# tps63020-buck-boost-flashlight-driver-17.net
KiCad netlist of a schematic drawn in EAGLE
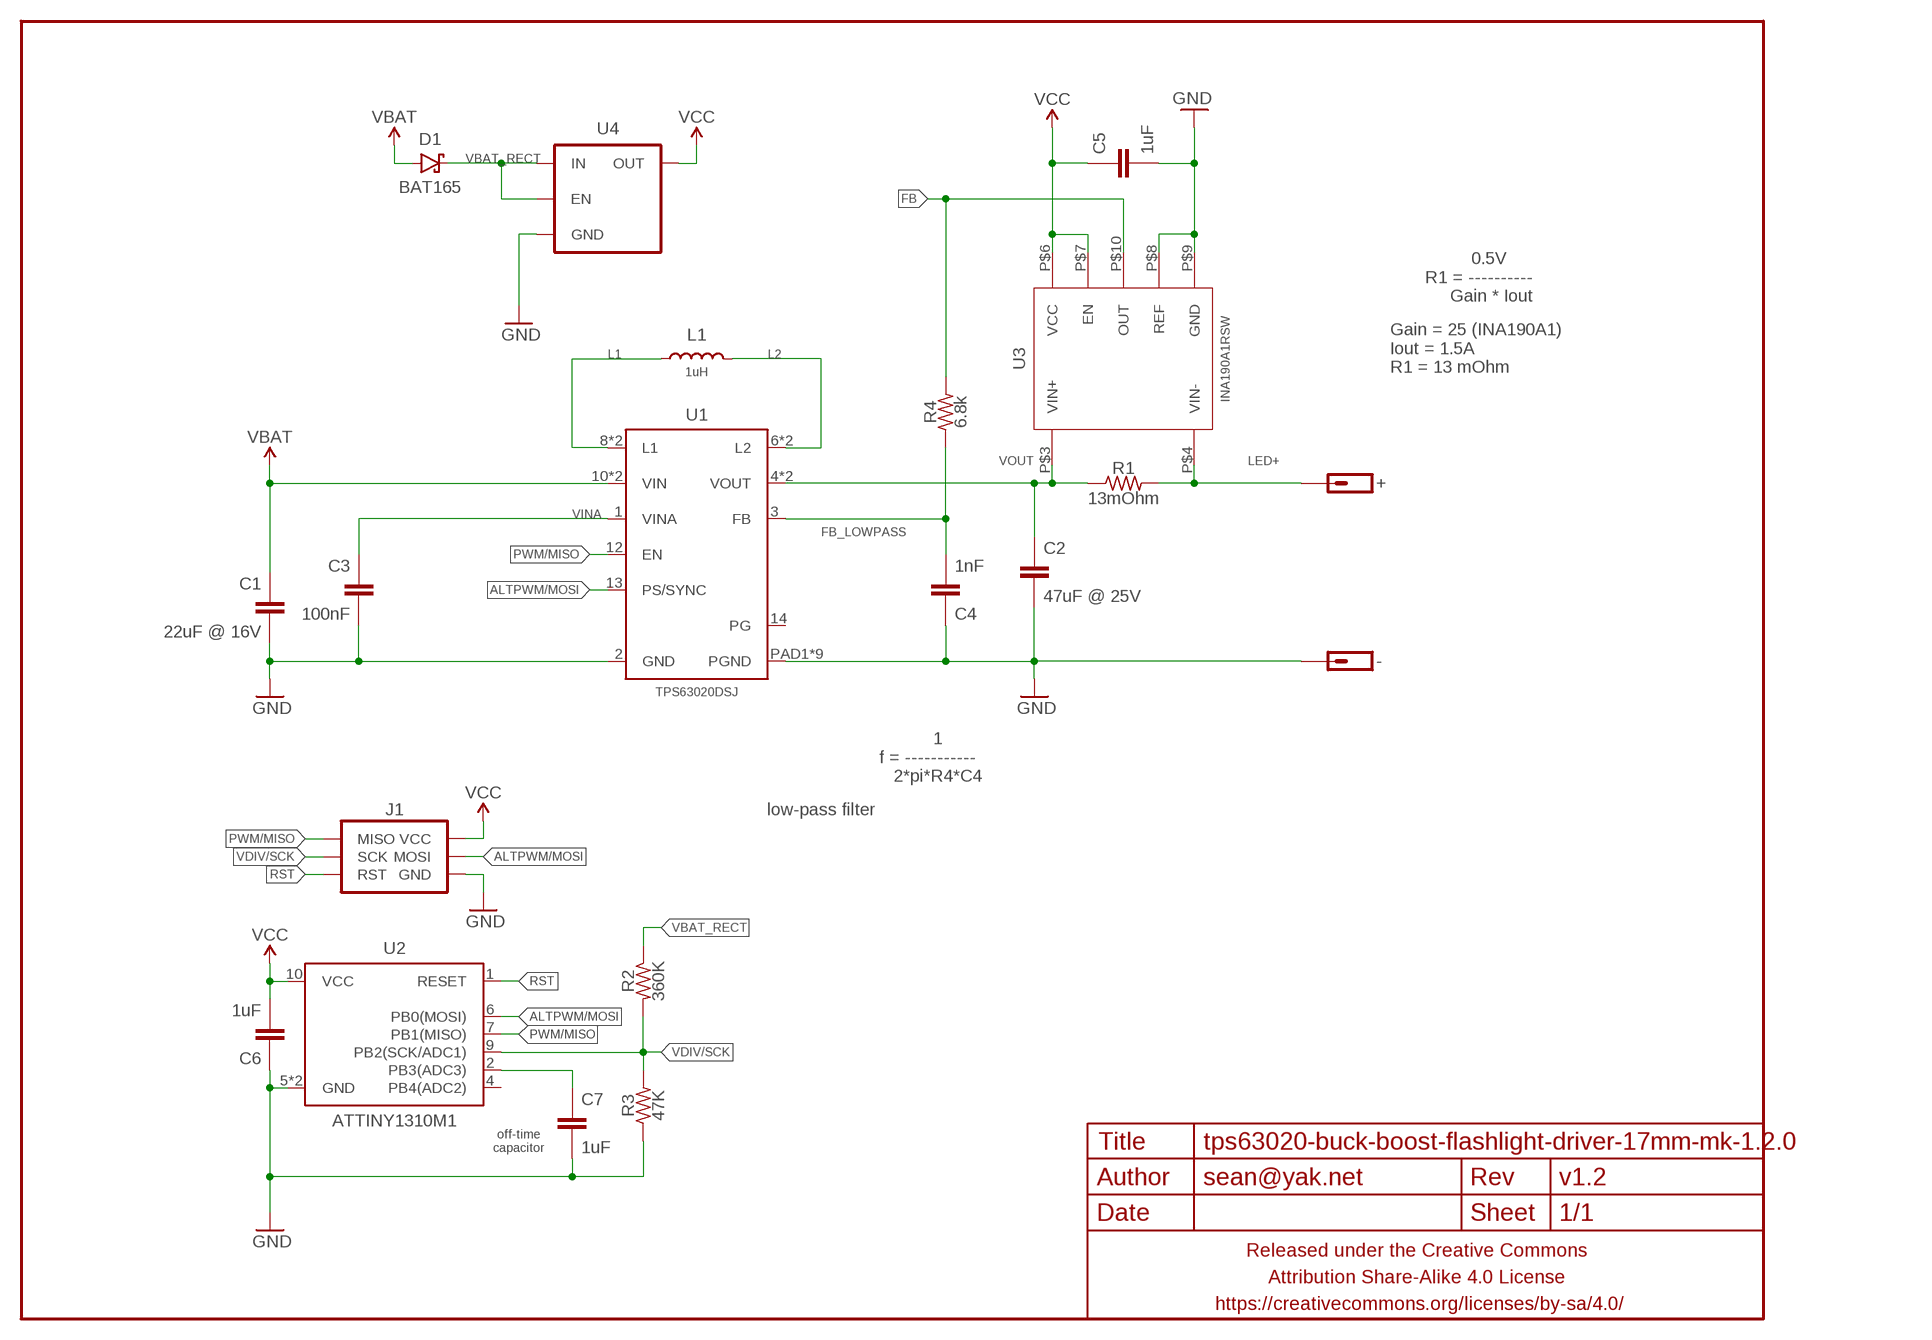
[diagram p0: schematic, sheet 1]

(export (version "E")
  (design (tool "Eeschema 10.0.6"))
  (components
    (comp (ref "+")
      (value "M01SMD-1.6MMX3.2MM")
      (footprint "eagle-import:1X01-SMD-1.6MMX3.2MM")
      (libsource (lib "eagle-import") (part "M01SMD-1.6MMX3.2MM"))
    )
    (comp (ref "-")
      (value "M01SMD-1.6MMX3.2MM")
      (footprint "eagle-import:1X01-SMD-1.6MMX3.2MM")
      (libsource (lib "eagle-import") (part "M01SMD-1.6MMX3.2MM"))
    )
    (comp (ref "C1")
      (value "22uF @ 16V")
      (footprint "eagle-import:C0805-TIGHTER")
      (libsource (lib "eagle-import") (part "CAPACITOR-CERAMICC0805-TIGHTER"))
    )
    (comp (ref "C2")
      (value "47uF @ 25V")
      (footprint "eagle-import:C1206")
      (libsource (lib "eagle-import") (part "CAPACITOR-CERAMICC1206"))
    )
    (comp (ref "C3")
      (value "100nF")
      (footprint "eagle-import:C0402")
      (libsource (lib "eagle-import") (part "CAPACITOR-CERAMICC0402"))
    )
    (comp (ref "C4")
      (value "1nF")
      (footprint "eagle-import:C0402")
      (libsource (lib "eagle-import") (part "CAPACITOR-CERAMICC0402"))
    )
    (comp (ref "C5")
      (value "1uF")
      (footprint "eagle-import:C0402")
      (libsource (lib "eagle-import") (part "CAPACITOR-CERAMICC0402"))
    )
    (comp (ref "C6")
      (value "1uF")
      (footprint "eagle-import:C0402")
      (libsource (lib "eagle-import") (part "CAPACITOR-CERAMICC0402"))
    )
    (comp (ref "C7")
      (value "1uF")
      (footprint "eagle-import:C0402")
      (libsource (lib "eagle-import") (part "CAPACITOR-CERAMICC0402"))
    )
    (comp (ref "D1")
      (value "BAT165")
      (footprint "eagle-import:SOD323-SCHOTTKY")
      (libsource (lib "eagle-import") (part "DIODE-SCHOTTKYSOD323"))
    )
    (comp (ref "FRAME1")
      (value "FRAME-LETTERNO_PACKAGE")
      (footprint "eagle-import:DUMMY")
      (fields
        (field (name "DESIGNER") "sean@yak.net")
        (field (name "VERSION") "v1.2")
        (field (name "DESIGNER_1") "sean@yak.net")
        (field (name "VERSION_1") "v1.2")
      )
      (libsource (lib "eagle-import") (part "FRAME-LETTERNO_PACKAGE"))
    )
    (comp (ref "J1")
      (value "AVR_SPI_PRG_6SMD-1.27MM")
      (footprint "eagle-import:2X3-1.27MM-SMD")
      (libsource (lib "eagle-import") (part "AVR_SPI_PRG_6SMD-1.27MM"))
    )
    (comp (ref "L1")
      (value "1uH")
      (footprint "eagle-import:XAL50X0")
      (libsource (lib "eagle-import") (part "INDUCTORXAL50X0"))
    )
    (comp (ref "R1")
      (value "13mOhm")
      (footprint "eagle-import:R1206")
      (libsource (lib "eagle-import") (part "RESISTORR1206"))
    )
    (comp (ref "R2")
      (value "360K")
      (footprint "eagle-import:R0402")
      (libsource (lib "eagle-import") (part "RESISTORR0402"))
    )
    (comp (ref "R3")
      (value "47K")
      (footprint "eagle-import:R0402")
      (libsource (lib "eagle-import") (part "RESISTORR0402"))
    )
    (comp (ref "R4")
      (value "6.8k")
      (footprint "eagle-import:R0402")
      (libsource (lib "eagle-import") (part "RESISTORR0402"))
    )
    (comp (ref "U1")
      (value "TPS63020DSJ")
      (footprint "eagle-import:VSON-14-4MMX3MM")
      (libsource (lib "eagle-import") (part "TPS63020DSJ"))
    )
    (comp (ref "U2")
      (value "ATTINY1310M1")
      (footprint "eagle-import:QFN10(2X5)")
      (libsource (lib "eagle-import") (part "ATTINY1310M1"))
    )
    (comp (ref "U3")
      (value "INA190A1RSW")
      (footprint "eagle-import:UQFN-10")
      (libsource (lib "eagle-import") (part "INA190RSW"))
    )
    (comp (ref "U4")
      (value "V_REG_ENTLV700")
      (footprint "eagle-import:SC70")
      (libsource (lib "eagle-import") (part "V_REG_ENTLV700"))
    )
  )
  (nets
    (net (code "1") (name "/FB_LOWPASS") (class "Default")
      (node (ref "C4") (pin "2") (pinfunction "2_2") (pintype "passive"))
      (node (ref "R4") (pin "1") (pinfunction "1_1") (pintype "passive"))
      (node (ref "U1") (pin "3") (pinfunction "FB_3") (pintype "bidirectional"))
    )
    (net (code "2") (name "/L1") (class "Default")
      (node (ref "L1") (pin "P$1") (pinfunction "1_P$1") (pintype "passive"))
      (node (ref "U1") (pin "8") (pinfunction "L1_8") (pintype "bidirectional"))
      (node (ref "U1") (pin "9") (pinfunction "L1_9") (pintype "bidirectional"))
    )
    (net (code "3") (name "/L2") (class "Default")
      (node (ref "L1") (pin "P$2") (pinfunction "2_P$2") (pintype "passive"))
      (node (ref "U1") (pin "6") (pinfunction "L2_6") (pintype "bidirectional"))
      (node (ref "U1") (pin "7") (pinfunction "L2_7") (pintype "bidirectional"))
    )
    (net (code "4") (name "/LED+") (class "Default")
      (node (ref "+") (pin "P$1") (pinfunction "1_P$1") (pintype "passive"))
      (node (ref "R1") (pin "2") (pinfunction "2_2") (pintype "passive"))
      (node (ref "U3") (pin "P$4") (pinfunction "VIN-_P$4") (pintype "bidirectional"))
    )
    (net (code "5") (name "/VINA") (class "Default")
      (node (ref "C3") (pin "1") (pinfunction "1_1") (pintype "passive"))
      (node (ref "U1") (pin "1") (pinfunction "VINA_1") (pintype "bidirectional"))
    )
    (net (code "6") (name "/VOUT") (class "Default")
      (node (ref "C2") (pin "1") (pinfunction "1_1") (pintype "passive"))
      (node (ref "R1") (pin "1") (pinfunction "1_1") (pintype "passive"))
      (node (ref "U1") (pin "4") (pinfunction "VOUT_4") (pintype "bidirectional"))
      (node (ref "U1") (pin "5") (pinfunction "VOUT_5") (pintype "bidirectional"))
      (node (ref "U3") (pin "P$3") (pinfunction "VIN+_P$3") (pintype "bidirectional"))
    )
    (net (code "7") (name "ALTPWM{slash}MOSI") (class "Default")
      (node (ref "J1") (pin "4") (pinfunction "MOSI_4") (pintype "passive"))
      (node (ref "U1") (pin "13") (pinfunction "PS/SYNC_13") (pintype "bidirectional"))
      (node (ref "U2") (pin "6") (pinfunction "PB0(MOSI)_6") (pintype "bidirectional"))
    )
    (net (code "8") (name "FB") (class "Default")
      (node (ref "R4") (pin "2") (pinfunction "2_2") (pintype "passive"))
      (node (ref "U3") (pin "P$10") (pinfunction "OUT_P$10") (pintype "bidirectional"))
    )
    (net (code "9") (name "GND") (class "Default")
      (node (ref "-") (pin "P$1") (pinfunction "1_P$1") (pintype "passive"))
      (node (ref "C1") (pin "2") (pinfunction "2_2") (pintype "passive"))
      (node (ref "C2") (pin "2") (pinfunction "2_2") (pintype "passive"))
      (node (ref "C3") (pin "2") (pinfunction "2_2") (pintype "passive"))
      (node (ref "C4") (pin "1") (pinfunction "1_1") (pintype "passive"))
      (node (ref "C5") (pin "2") (pinfunction "2_2") (pintype "passive"))
      (node (ref "C6") (pin "1") (pinfunction "1_1") (pintype "passive"))
      (node (ref "C7") (pin "2") (pinfunction "2_2") (pintype "passive"))
      (node (ref "J1") (pin "6") (pinfunction "GND_6") (pintype "passive"))
      (node (ref "R3") (pin "1") (pinfunction "1_1") (pintype "passive"))
      (node (ref "U1") (pin "2") (pinfunction "GND_2") (pintype "bidirectional"))
      (node (ref "U1") (pin "PAD1") (pinfunction "PGND_PAD1") (pintype "bidirectional"))
      (node (ref "U1") (pin "PAD2") (pinfunction "PGND_PAD2") (pintype "bidirectional"))
      (node (ref "U1") (pin "PAD3") (pinfunction "PGND_PAD3") (pintype "bidirectional"))
      (node (ref "U1") (pin "PAD4") (pinfunction "PGND_PAD4") (pintype "bidirectional"))
      (node (ref "U1") (pin "PAD5") (pinfunction "PGND_PAD5") (pintype "bidirectional"))
      (node (ref "U1") (pin "PAD6") (pinfunction "PGND_PAD6") (pintype "bidirectional"))
      (node (ref "U1") (pin "PAD7") (pinfunction "PGND_PAD7") (pintype "bidirectional"))
      (node (ref "U1") (pin "PAD8") (pinfunction "PGND_PAD8") (pintype "bidirectional"))
      (node (ref "U1") (pin "PADCENTER") (pinfunction "PGND_PADCENTER") (pintype "bidirectional"))
      (node (ref "U2") (pin "5") (pinfunction "GND_5") (pintype "bidirectional"))
      (node (ref "U2") (pin "PAD") (pinfunction "GND_PAD") (pintype "bidirectional"))
      (node (ref "U3") (pin "P$8") (pinfunction "REF_P$8") (pintype "bidirectional"))
      (node (ref "U3") (pin "P$9") (pinfunction "GND_P$9") (pintype "bidirectional"))
      (node (ref "U4") (pin "2") (pinfunction "GND_2") (pintype "input"))
    )
    (net (code "10") (name "Net-(U2-PB3(ADC3))") (class "Default")
      (node (ref "C7") (pin "1") (pinfunction "1_1") (pintype "passive"))
      (node (ref "U2") (pin "2") (pinfunction "PB3(ADC3)_2") (pintype "bidirectional"))
    )
    (net (code "11") (name "PWM{slash}MISO") (class "Default")
      (node (ref "J1") (pin "1") (pinfunction "MISO_1") (pintype "passive"))
      (node (ref "U1") (pin "12") (pinfunction "EN_12") (pintype "bidirectional"))
      (node (ref "U2") (pin "7") (pinfunction "PB1(MISO)_7") (pintype "bidirectional"))
    )
    (net (code "12") (name "RST") (class "Default")
      (node (ref "J1") (pin "5") (pinfunction "RST_5") (pintype "passive"))
      (node (ref "U2") (pin "1") (pinfunction "RESET_1") (pintype "bidirectional"))
    )
    (net (code "13") (name "VBAT") (class "Default")
      (node (ref "C1") (pin "1") (pinfunction "1_1") (pintype "passive"))
      (node (ref "D1") (pin "A") (pinfunction "A_A") (pintype "passive"))
      (node (ref "U1") (pin "10") (pinfunction "VIN_10") (pintype "bidirectional"))
      (node (ref "U1") (pin "11") (pinfunction "VIN_11") (pintype "bidirectional"))
    )
    (net (code "14") (name "VBAT_RECT") (class "Default")
      (node (ref "D1") (pin "C") (pinfunction "C_C") (pintype "passive"))
      (node (ref "R2") (pin "1") (pinfunction "1_1") (pintype "passive"))
      (node (ref "U4") (pin "1") (pinfunction "IN_1") (pintype "input"))
      (node (ref "U4") (pin "3") (pinfunction "EN_3") (pintype "input"))
    )
    (net (code "15") (name "VCC") (class "Default")
      (node (ref "C5") (pin "1") (pinfunction "1_1") (pintype "passive"))
      (node (ref "C6") (pin "2") (pinfunction "2_2") (pintype "passive"))
      (node (ref "J1") (pin "2") (pinfunction "VCC_2") (pintype "passive"))
      (node (ref "U2") (pin "10") (pinfunction "VCC_10") (pintype "bidirectional"))
      (node (ref "U3") (pin "P$6") (pinfunction "VCC_P$6") (pintype "bidirectional"))
      (node (ref "U3") (pin "P$7") (pinfunction "EN_P$7") (pintype "bidirectional"))
      (node (ref "U4") (pin "5") (pinfunction "OUT_5") (pintype "passive"))
    )
    (net (code "16") (name "VDIV{slash}SCK") (class "Default")
      (node (ref "J1") (pin "3") (pinfunction "SCK_3") (pintype "passive"))
      (node (ref "R2") (pin "2") (pinfunction "2_2") (pintype "passive"))
      (node (ref "R3") (pin "2") (pinfunction "2_2") (pintype "passive"))
      (node (ref "U2") (pin "9") (pinfunction "PB2(SCK/ADC1)_9") (pintype "bidirectional"))
    )
    (net (code "17") (name "unconnected-(U1-PG-Pad14)") (class "Default")
      (node (ref "U1") (pin "14") (pinfunction "PG_14") (pintype "bidirectional"))
    )
    (net (code "18") (name "unconnected-(U2-PB4(ADC2)-Pad4)") (class "Default")
      (node (ref "U2") (pin "4") (pinfunction "PB4(ADC2)_4") (pintype "bidirectional"))
    )
  )
)
